# main.net
KiCad netlist of a schematic drawn in EAGLE
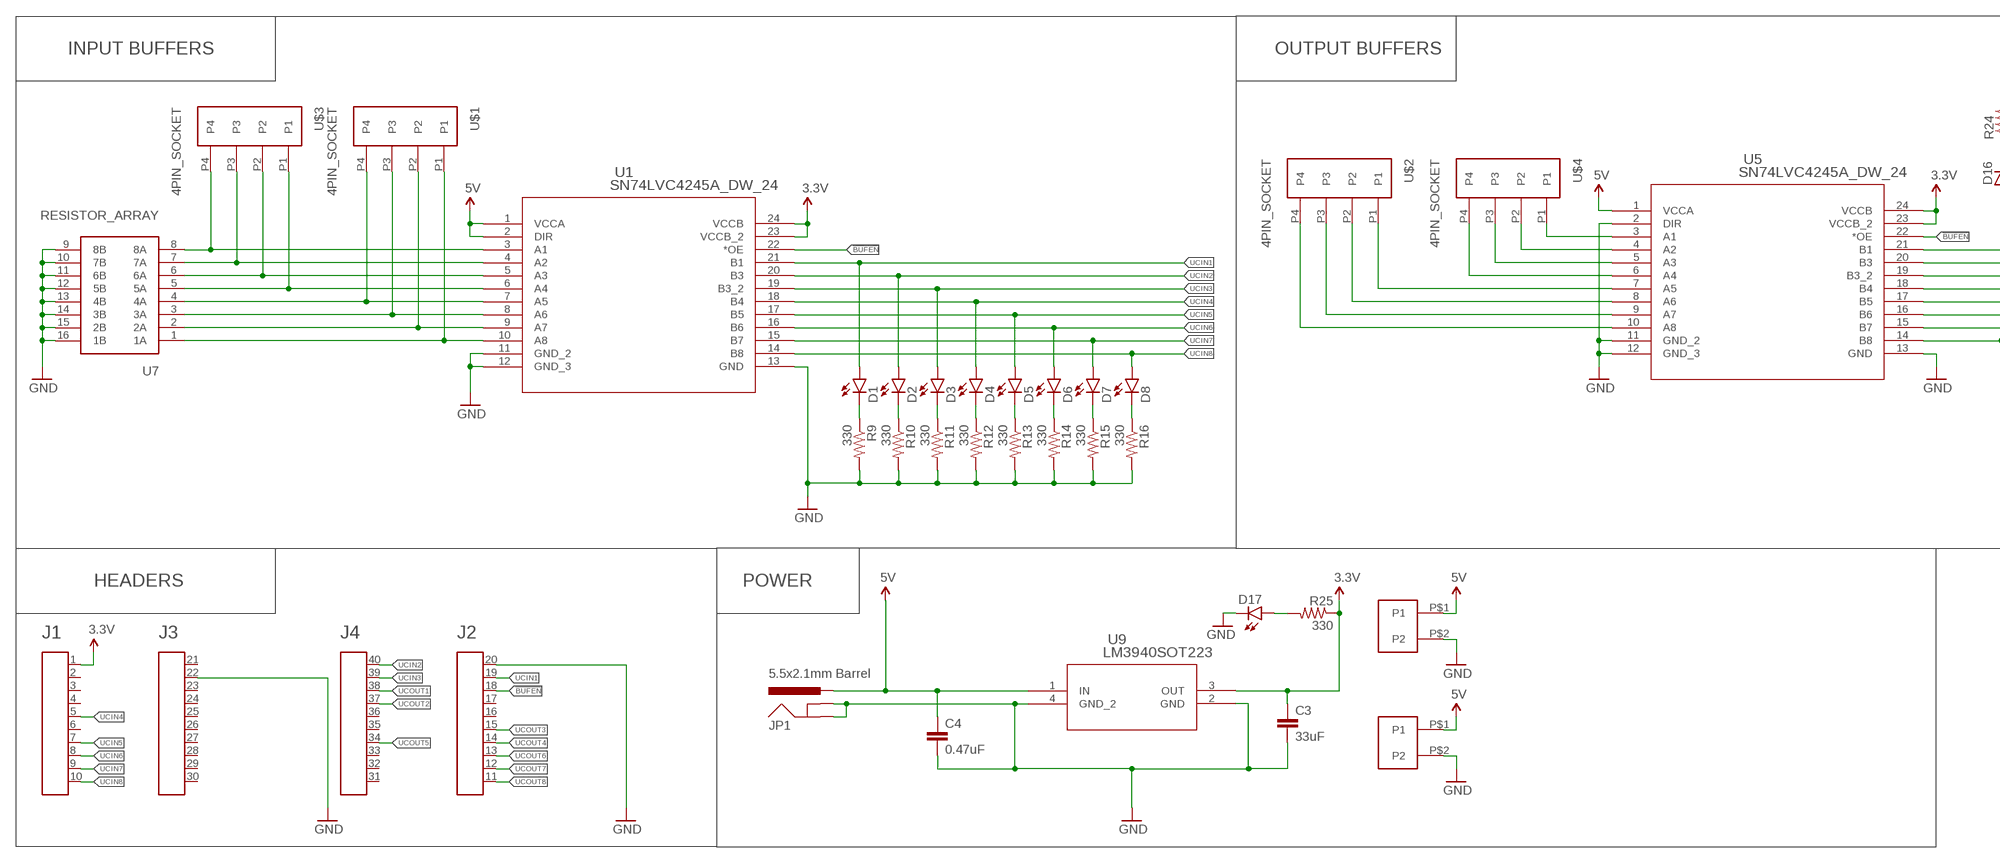
[diagram p0: schematic, sheet 1, part 1 of 2]
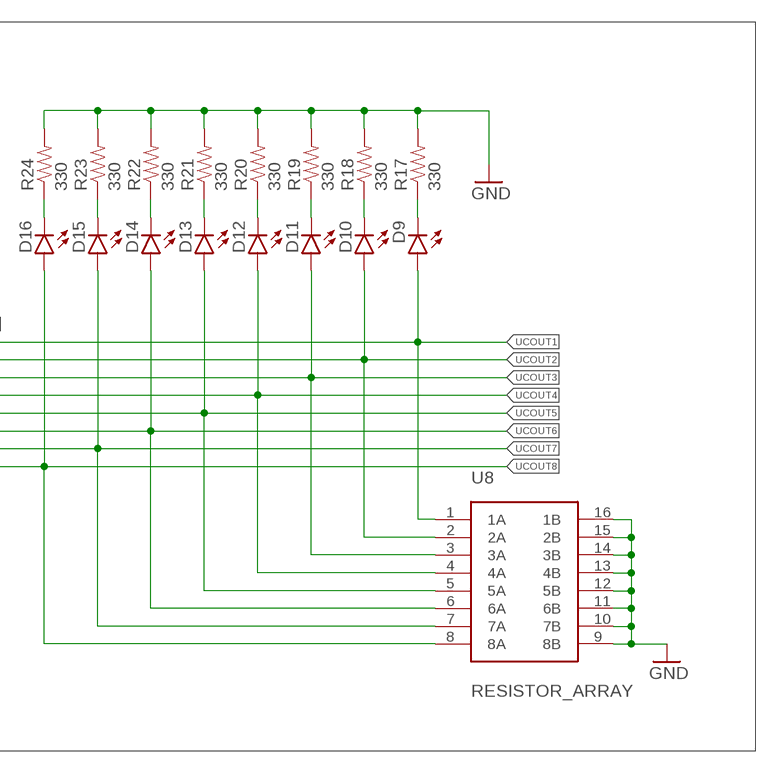
[diagram p1: schematic, sheet 1, part 2 of 2]

(export (version "E")
  (design (tool "Eeschema 10.0.6"))
  (components
    (comp (ref "A1")
      (value "HEADER4X10-BOOSTERPACK")
      (footprint "eagle-import:4X10-BOOSTERPACK")
      (libsource (lib "eagle-import") (part "HEADER4X10-BOOSTERPACK"))
    )
    (comp (ref "C3")
      (value "33uF")
      (footprint "eagle-import:1206")
      (libsource (lib "eagle-import") (part "2.2UF50V10%(1206)"))
    )
    (comp (ref "C4")
      (value "0.47uF")
      (footprint "eagle-import:0805")
      (libsource (lib "eagle-import") (part "1.0UF-25V-+80/-20(0805)"))
    )
    (comp (ref "D1")
      (value "LED3MM")
      (footprint "eagle-import:LED3MM")
      (libsource (lib "eagle-import") (part "LED3MM"))
    )
    (comp (ref "D2")
      (value "LED3MM")
      (footprint "eagle-import:LED3MM")
      (libsource (lib "eagle-import") (part "LED3MM"))
    )
    (comp (ref "D3")
      (value "LED3MM")
      (footprint "eagle-import:LED3MM")
      (libsource (lib "eagle-import") (part "LED3MM"))
    )
    (comp (ref "D4")
      (value "LED3MM")
      (footprint "eagle-import:LED3MM")
      (libsource (lib "eagle-import") (part "LED3MM"))
    )
    (comp (ref "D5")
      (value "LED3MM")
      (footprint "eagle-import:LED3MM")
      (libsource (lib "eagle-import") (part "LED3MM"))
    )
    (comp (ref "D6")
      (value "LED3MM")
      (footprint "eagle-import:LED3MM")
      (libsource (lib "eagle-import") (part "LED3MM"))
    )
    (comp (ref "D7")
      (value "LED3MM")
      (footprint "eagle-import:LED3MM")
      (libsource (lib "eagle-import") (part "LED3MM"))
    )
    (comp (ref "D8")
      (value "LED3MM")
      (footprint "eagle-import:LED3MM")
      (libsource (lib "eagle-import") (part "LED3MM"))
    )
    (comp (ref "D9")
      (value "LED3MM")
      (footprint "eagle-import:LED3MM")
      (libsource (lib "eagle-import") (part "LED3MM"))
    )
    (comp (ref "D10")
      (value "LED3MM")
      (footprint "eagle-import:LED3MM")
      (libsource (lib "eagle-import") (part "LED3MM"))
    )
    (comp (ref "D11")
      (value "LED3MM")
      (footprint "eagle-import:LED3MM")
      (libsource (lib "eagle-import") (part "LED3MM"))
    )
    (comp (ref "D12")
      (value "LED3MM")
      (footprint "eagle-import:LED3MM")
      (libsource (lib "eagle-import") (part "LED3MM"))
    )
    (comp (ref "D13")
      (value "LED3MM")
      (footprint "eagle-import:LED3MM")
      (libsource (lib "eagle-import") (part "LED3MM"))
    )
    (comp (ref "D14")
      (value "LED3MM")
      (footprint "eagle-import:LED3MM")
      (libsource (lib "eagle-import") (part "LED3MM"))
    )
    (comp (ref "D15")
      (value "LED3MM")
      (footprint "eagle-import:LED3MM")
      (libsource (lib "eagle-import") (part "LED3MM"))
    )
    (comp (ref "D16")
      (value "LED3MM")
      (footprint "eagle-import:LED3MM")
      (libsource (lib "eagle-import") (part "LED3MM"))
    )
    (comp (ref "D17")
      (value "LED3MM")
      (footprint "eagle-import:LED3MM")
      (libsource (lib "eagle-import") (part "LED3MM"))
    )
    (comp (ref "JP1")
      (value "5.5x2.1mm Barrel")
      (footprint "eagle-import:POWER_JACK_SMD")
      (libsource (lib "eagle-import") (part "POWER_JACKSMD"))
    )
    (comp (ref "R9")
      (value "330")
      (footprint "eagle-import:0805")
      (libsource (lib "eagle-import") (part "RESISTOR0805-RES"))
    )
    (comp (ref "R10")
      (value "330")
      (footprint "eagle-import:0805")
      (libsource (lib "eagle-import") (part "RESISTOR0805-RES"))
    )
    (comp (ref "R11")
      (value "330")
      (footprint "eagle-import:0805")
      (libsource (lib "eagle-import") (part "RESISTOR0805-RES"))
    )
    (comp (ref "R12")
      (value "330")
      (footprint "eagle-import:0805")
      (libsource (lib "eagle-import") (part "RESISTOR0805-RES"))
    )
    (comp (ref "R13")
      (value "330")
      (footprint "eagle-import:0805")
      (libsource (lib "eagle-import") (part "RESISTOR0805-RES"))
    )
    (comp (ref "R14")
      (value "330")
      (footprint "eagle-import:0805")
      (libsource (lib "eagle-import") (part "RESISTOR0805-RES"))
    )
    (comp (ref "R15")
      (value "330")
      (footprint "eagle-import:0805")
      (libsource (lib "eagle-import") (part "RESISTOR0805-RES"))
    )
    (comp (ref "R16")
      (value "330")
      (footprint "eagle-import:0805")
      (libsource (lib "eagle-import") (part "RESISTOR0805-RES"))
    )
    (comp (ref "R17")
      (value "330")
      (footprint "eagle-import:0805")
      (libsource (lib "eagle-import") (part "RESISTOR0805-RES"))
    )
    (comp (ref "R18")
      (value "330")
      (footprint "eagle-import:0805")
      (libsource (lib "eagle-import") (part "RESISTOR0805-RES"))
    )
    (comp (ref "R19")
      (value "330")
      (footprint "eagle-import:0805")
      (libsource (lib "eagle-import") (part "RESISTOR0805-RES"))
    )
    (comp (ref "R20")
      (value "330")
      (footprint "eagle-import:0805")
      (libsource (lib "eagle-import") (part "RESISTOR0805-RES"))
    )
    (comp (ref "R21")
      (value "330")
      (footprint "eagle-import:0805")
      (libsource (lib "eagle-import") (part "RESISTOR0805-RES"))
    )
    (comp (ref "R22")
      (value "330")
      (footprint "eagle-import:0805")
      (libsource (lib "eagle-import") (part "RESISTOR0805-RES"))
    )
    (comp (ref "R23")
      (value "330")
      (footprint "eagle-import:0805")
      (libsource (lib "eagle-import") (part "RESISTOR0805-RES"))
    )
    (comp (ref "R24")
      (value "330")
      (footprint "eagle-import:0805")
      (libsource (lib "eagle-import") (part "RESISTOR0805-RES"))
    )
    (comp (ref "R25")
      (value "330")
      (footprint "eagle-import:0805")
      (libsource (lib "eagle-import") (part "RESISTOR0805-RES"))
    )
    (comp (ref "U$1")
      (value "4PIN_SOCKET")
      (footprint "eagle-import:CONN-4PIN")
      (libsource (lib "eagle-import") (part "4PIN_SOCKET"))
    )
    (comp (ref "U$2")
      (value "4PIN_SOCKET")
      (footprint "eagle-import:CONN-4PIN")
      (libsource (lib "eagle-import") (part "4PIN_SOCKET"))
    )
    (comp (ref "U$3")
      (value "4PIN_SOCKET")
      (footprint "eagle-import:CONN-4PIN")
      (libsource (lib "eagle-import") (part "4PIN_SOCKET"))
    )
    (comp (ref "U$4")
      (value "4PIN_SOCKET")
      (footprint "eagle-import:CONN-4PIN")
      (libsource (lib "eagle-import") (part "4PIN_SOCKET"))
    )
    (comp (ref "U$5")
      (value "2PIN_SOCKET")
      (footprint "eagle-import:CONN-2PIN")
      (libsource (lib "eagle-import") (part "2PIN_SOCKET"))
    )
    (comp (ref "U$6")
      (value "2PIN_SOCKET")
      (footprint "eagle-import:CONN-2PIN")
      (libsource (lib "eagle-import") (part "2PIN_SOCKET"))
    )
    (comp (ref "U1")
      (value "SN74LVC4245A_DW_24")
      (footprint "eagle-import:DW24")
      (fields
        (field (name "GENERIC_PART_NUMBER") "SN74LVC4245A")
        (field (name "MANUFACTURER") "Texas Instruments")
        (field (name "MANUFACTURER_PART_NUMBER") "sn74lvc4245a_dw_24")
      )
      (libsource (lib "eagle-import") (part "SN74LVC4245A_DW_24"))
    )
    (comp (ref "U5")
      (value "SN74LVC4245A_DW_24")
      (footprint "eagle-import:DW24")
      (fields
        (field (name "GENERIC_PART_NUMBER") "SN74LVC4245A")
        (field (name "MANUFACTURER") "Texas Instruments")
        (field (name "MANUFACTURER_PART_NUMBER") "sn74lvc4245a_dw_24")
      )
      (libsource (lib "eagle-import") (part "SN74LVC4245A_DW_24"))
    )
    (comp (ref "U7")
      (value "RESISTOR_ARRAY")
      (footprint "eagle-import:DIL16")
      (libsource (lib "eagle-import") (part "RESISTOR_ARRAY"))
    )
    (comp (ref "U8")
      (value "RESISTOR_ARRAY")
      (footprint "eagle-import:DIL16")
      (libsource (lib "eagle-import") (part "RESISTOR_ARRAY"))
    )
    (comp (ref "U9")
      (value "LM3940SOT223")
      (footprint "eagle-import:DCY")
      (libsource (lib "eagle-import") (part "LM3940SOT223"))
    )
  )
  (nets
    (net (code "1") (name "/~{BUFEN}") (class "Default")
      (node (ref "A1") (pin "18") (pinfunction "P$18_18") (pintype "bidirectional"))
      (node (ref "U1") (pin "22") (pinfunction "*OE_22") (pintype "input"))
      (node (ref "U5") (pin "22") (pinfunction "*OE_22") (pintype "input"))
    )
    (net (code "2") (name "3.3V") (class "Default")
      (node (ref "A1") (pin "1") (pinfunction "P$1_1") (pintype "bidirectional"))
      (node (ref "C3") (pin "1") (pinfunction "1_1") (pintype "passive"))
      (node (ref "R25") (pin "1") (pinfunction "1_1") (pintype "passive"))
      (node (ref "U1") (pin "23") (pinfunction "VCCB_2_23") (pintype "power_in"))
      (node (ref "U1") (pin "24") (pinfunction "VCCB_24") (pintype "power_in"))
      (node (ref "U5") (pin "23") (pinfunction "VCCB_2_23") (pintype "power_in"))
      (node (ref "U5") (pin "24") (pinfunction "VCCB_24") (pintype "power_in"))
      (node (ref "U9") (pin "3") (pinfunction "OUT_3") (pintype "output"))
    )
    (net (code "3") (name "5V") (class "Default")
      (node (ref "C4") (pin "1") (pinfunction "1_1") (pintype "passive"))
      (node (ref "JP1") (pin "VIN0") (pinfunction "PWR_VIN0") (pintype "bidirectional"))
      (node (ref "U$5") (pin "P$1") (pinfunction "P1_P$1") (pintype "bidirectional"))
      (node (ref "U$6") (pin "P$1") (pinfunction "P1_P$1") (pintype "bidirectional"))
      (node (ref "U1") (pin "1") (pinfunction "VCCA_1") (pintype "power_in"))
      (node (ref "U1") (pin "2") (pinfunction "DIR_2") (pintype "input"))
      (node (ref "U5") (pin "1") (pinfunction "VCCA_1") (pintype "power_in"))
      (node (ref "U9") (pin "1") (pinfunction "IN_1") (pintype "input"))
    )
    (net (code "4") (name "GND") (class "Default")
      (node (ref "A1") (pin "20") (pinfunction "P$20_20") (pintype "bidirectional"))
      (node (ref "A1") (pin "22") (pinfunction "P$22_22") (pintype "bidirectional"))
      (node (ref "C3") (pin "2") (pinfunction "2_2") (pintype "passive"))
      (node (ref "C4") (pin "2") (pinfunction "2_2") (pintype "passive"))
      (node (ref "D17") (pin "K") (pinfunction "C_K") (pintype "passive"))
      (node (ref "JP1") (pin "GND") (pinfunction "GNDBREAK_GND") (pintype "bidirectional"))
      (node (ref "JP1") (pin "P$4") (pinfunction "GND_P$4") (pintype "bidirectional"))
      (node (ref "R10") (pin "2") (pinfunction "2_2") (pintype "passive"))
      (node (ref "R11") (pin "2") (pinfunction "2_2") (pintype "passive"))
      (node (ref "R12") (pin "2") (pinfunction "2_2") (pintype "passive"))
      (node (ref "R13") (pin "2") (pinfunction "2_2") (pintype "passive"))
      (node (ref "R14") (pin "2") (pinfunction "2_2") (pintype "passive"))
      (node (ref "R15") (pin "2") (pinfunction "2_2") (pintype "passive"))
      (node (ref "R16") (pin "2") (pinfunction "2_2") (pintype "passive"))
      (node (ref "R17") (pin "2") (pinfunction "2_2") (pintype "passive"))
      (node (ref "R18") (pin "2") (pinfunction "2_2") (pintype "passive"))
      (node (ref "R19") (pin "2") (pinfunction "2_2") (pintype "passive"))
      (node (ref "R20") (pin "2") (pinfunction "2_2") (pintype "passive"))
      (node (ref "R21") (pin "2") (pinfunction "2_2") (pintype "passive"))
      (node (ref "R22") (pin "2") (pinfunction "2_2") (pintype "passive"))
      (node (ref "R23") (pin "2") (pinfunction "2_2") (pintype "passive"))
      (node (ref "R24") (pin "2") (pinfunction "2_2") (pintype "passive"))
      (node (ref "R9") (pin "2") (pinfunction "2_2") (pintype "passive"))
      (node (ref "U$5") (pin "P$2") (pinfunction "P2_P$2") (pintype "bidirectional"))
      (node (ref "U$6") (pin "P$2") (pinfunction "P2_P$2") (pintype "bidirectional"))
      (node (ref "U1") (pin "11") (pinfunction "GND_2_11") (pintype "power_in"))
      (node (ref "U1") (pin "12") (pinfunction "GND_3_12") (pintype "power_in"))
      (node (ref "U1") (pin "13") (pinfunction "GND_13") (pintype "power_in"))
      (node (ref "U5") (pin "11") (pinfunction "GND_2_11") (pintype "power_in"))
      (node (ref "U5") (pin "12") (pinfunction "GND_3_12") (pintype "power_in"))
      (node (ref "U5") (pin "13") (pinfunction "GND_13") (pintype "power_in"))
      (node (ref "U5") (pin "2") (pinfunction "DIR_2") (pintype "input"))
      (node (ref "U7") (pin "10") (pinfunction "7B_10") (pintype "bidirectional"))
      (node (ref "U7") (pin "11") (pinfunction "6B_11") (pintype "bidirectional"))
      (node (ref "U7") (pin "12") (pinfunction "5B_12") (pintype "bidirectional"))
      (node (ref "U7") (pin "13") (pinfunction "4B_13") (pintype "bidirectional"))
      (node (ref "U7") (pin "14") (pinfunction "3B_14") (pintype "bidirectional"))
      (node (ref "U7") (pin "15") (pinfunction "2B_15") (pintype "bidirectional"))
      (node (ref "U7") (pin "16") (pinfunction "1B_16") (pintype "bidirectional"))
      (node (ref "U7") (pin "9") (pinfunction "8B_9") (pintype "bidirectional"))
      (node (ref "U8") (pin "10") (pinfunction "7B_10") (pintype "bidirectional"))
      (node (ref "U8") (pin "11") (pinfunction "6B_11") (pintype "bidirectional"))
      (node (ref "U8") (pin "12") (pinfunction "5B_12") (pintype "bidirectional"))
      (node (ref "U8") (pin "13") (pinfunction "4B_13") (pintype "bidirectional"))
      (node (ref "U8") (pin "14") (pinfunction "3B_14") (pintype "bidirectional"))
      (node (ref "U8") (pin "15") (pinfunction "2B_15") (pintype "bidirectional"))
      (node (ref "U8") (pin "16") (pinfunction "1B_16") (pintype "bidirectional"))
      (node (ref "U8") (pin "9") (pinfunction "8B_9") (pintype "bidirectional"))
      (node (ref "U9") (pin "2") (pinfunction "GND_2") (pintype "passive"))
      (node (ref "U9") (pin "4") (pinfunction "GND_2_4") (pintype "passive"))
    )
    (net (code "5") (name "Net-(D1-C)") (class "Default")
      (node (ref "D1") (pin "K") (pinfunction "C_K") (pintype "passive"))
      (node (ref "R9") (pin "1") (pinfunction "1_1") (pintype "passive"))
    )
    (net (code "6") (name "Net-(D2-C)") (class "Default")
      (node (ref "D2") (pin "K") (pinfunction "C_K") (pintype "passive"))
      (node (ref "R10") (pin "1") (pinfunction "1_1") (pintype "passive"))
    )
    (net (code "7") (name "Net-(D3-C)") (class "Default")
      (node (ref "D3") (pin "K") (pinfunction "C_K") (pintype "passive"))
      (node (ref "R11") (pin "1") (pinfunction "1_1") (pintype "passive"))
    )
    (net (code "8") (name "Net-(D4-C)") (class "Default")
      (node (ref "D4") (pin "K") (pinfunction "C_K") (pintype "passive"))
      (node (ref "R12") (pin "1") (pinfunction "1_1") (pintype "passive"))
    )
    (net (code "9") (name "Net-(D5-C)") (class "Default")
      (node (ref "D5") (pin "K") (pinfunction "C_K") (pintype "passive"))
      (node (ref "R13") (pin "1") (pinfunction "1_1") (pintype "passive"))
    )
    (net (code "10") (name "Net-(D6-C)") (class "Default")
      (node (ref "D6") (pin "K") (pinfunction "C_K") (pintype "passive"))
      (node (ref "R14") (pin "1") (pinfunction "1_1") (pintype "passive"))
    )
    (net (code "11") (name "Net-(D7-C)") (class "Default")
      (node (ref "D7") (pin "K") (pinfunction "C_K") (pintype "passive"))
      (node (ref "R15") (pin "1") (pinfunction "1_1") (pintype "passive"))
    )
    (net (code "12") (name "Net-(D8-C)") (class "Default")
      (node (ref "D8") (pin "K") (pinfunction "C_K") (pintype "passive"))
      (node (ref "R16") (pin "1") (pinfunction "1_1") (pintype "passive"))
    )
    (net (code "13") (name "Net-(D9-C)") (class "Default")
      (node (ref "D9") (pin "K") (pinfunction "C_K") (pintype "passive"))
      (node (ref "R17") (pin "1") (pinfunction "1_1") (pintype "passive"))
    )
    (net (code "14") (name "Net-(D10-C)") (class "Default")
      (node (ref "D10") (pin "K") (pinfunction "C_K") (pintype "passive"))
      (node (ref "R18") (pin "1") (pinfunction "1_1") (pintype "passive"))
    )
    (net (code "15") (name "Net-(D11-C)") (class "Default")
      (node (ref "D11") (pin "K") (pinfunction "C_K") (pintype "passive"))
      (node (ref "R19") (pin "1") (pinfunction "1_1") (pintype "passive"))
    )
    (net (code "16") (name "Net-(D12-C)") (class "Default")
      (node (ref "D12") (pin "K") (pinfunction "C_K") (pintype "passive"))
      (node (ref "R20") (pin "1") (pinfunction "1_1") (pintype "passive"))
    )
    (net (code "17") (name "Net-(D13-C)") (class "Default")
      (node (ref "D13") (pin "K") (pinfunction "C_K") (pintype "passive"))
      (node (ref "R21") (pin "1") (pinfunction "1_1") (pintype "passive"))
    )
    (net (code "18") (name "Net-(D14-C)") (class "Default")
      (node (ref "D14") (pin "K") (pinfunction "C_K") (pintype "passive"))
      (node (ref "R22") (pin "1") (pinfunction "1_1") (pintype "passive"))
    )
    (net (code "19") (name "Net-(D15-C)") (class "Default")
      (node (ref "D15") (pin "K") (pinfunction "C_K") (pintype "passive"))
      (node (ref "R23") (pin "1") (pinfunction "1_1") (pintype "passive"))
    )
    (net (code "20") (name "Net-(D16-C)") (class "Default")
      (node (ref "D16") (pin "K") (pinfunction "C_K") (pintype "passive"))
      (node (ref "R24") (pin "1") (pinfunction "1_1") (pintype "passive"))
    )
    (net (code "21") (name "Net-(D17-PadA)") (class "Default")
      (node (ref "D17") (pin "A") (pinfunction "A_A") (pintype "passive"))
      (node (ref "R25") (pin "2") (pinfunction "2_2") (pintype "passive"))
    )
    (net (code "22") (name "Net-(U1-A1)") (class "Default")
      (node (ref "U$3") (pin "P4") (pinfunction "P4_P4") (pintype "bidirectional"))
      (node (ref "U1") (pin "3") (pinfunction "A1_3") (pintype "bidirectional"))
      (node (ref "U7") (pin "8") (pinfunction "8A_8") (pintype "bidirectional"))
    )
    (net (code "23") (name "Net-(U1-A2)") (class "Default")
      (node (ref "U$3") (pin "P3") (pinfunction "P3_P3") (pintype "bidirectional"))
      (node (ref "U1") (pin "4") (pinfunction "A2_4") (pintype "bidirectional"))
      (node (ref "U7") (pin "7") (pinfunction "7A_7") (pintype "bidirectional"))
    )
    (net (code "24") (name "Net-(U1-A3)") (class "Default")
      (node (ref "U$3") (pin "P2") (pinfunction "P2_P2") (pintype "bidirectional"))
      (node (ref "U1") (pin "5") (pinfunction "A3_5") (pintype "bidirectional"))
      (node (ref "U7") (pin "6") (pinfunction "6A_6") (pintype "bidirectional"))
    )
    (net (code "25") (name "Net-(U1-A4)") (class "Default")
      (node (ref "U$3") (pin "P1") (pinfunction "P1_P1") (pintype "bidirectional"))
      (node (ref "U1") (pin "6") (pinfunction "A4_6") (pintype "bidirectional"))
      (node (ref "U7") (pin "5") (pinfunction "5A_5") (pintype "bidirectional"))
    )
    (net (code "26") (name "Net-(U1-A5)") (class "Default")
      (node (ref "U$1") (pin "P4") (pinfunction "P4_P4") (pintype "bidirectional"))
      (node (ref "U1") (pin "7") (pinfunction "A5_7") (pintype "bidirectional"))
      (node (ref "U7") (pin "4") (pinfunction "4A_4") (pintype "bidirectional"))
    )
    (net (code "27") (name "Net-(U1-A6)") (class "Default")
      (node (ref "U$1") (pin "P3") (pinfunction "P3_P3") (pintype "bidirectional"))
      (node (ref "U1") (pin "8") (pinfunction "A6_8") (pintype "bidirectional"))
      (node (ref "U7") (pin "3") (pinfunction "3A_3") (pintype "bidirectional"))
    )
    (net (code "28") (name "Net-(U1-A7)") (class "Default")
      (node (ref "U$1") (pin "P2") (pinfunction "P2_P2") (pintype "bidirectional"))
      (node (ref "U1") (pin "9") (pinfunction "A7_9") (pintype "bidirectional"))
      (node (ref "U7") (pin "2") (pinfunction "2A_2") (pintype "bidirectional"))
    )
    (net (code "29") (name "Net-(U1-A8)") (class "Default")
      (node (ref "U$1") (pin "P1") (pinfunction "P1_P1") (pintype "bidirectional"))
      (node (ref "U1") (pin "10") (pinfunction "A8_10") (pintype "bidirectional"))
      (node (ref "U7") (pin "1") (pinfunction "1A_1") (pintype "bidirectional"))
    )
    (net (code "30") (name "Net-(U5-A1)") (class "Default")
      (node (ref "U$4") (pin "P1") (pinfunction "P1_P1") (pintype "bidirectional"))
      (node (ref "U5") (pin "3") (pinfunction "A1_3") (pintype "bidirectional"))
    )
    (net (code "31") (name "Net-(U5-A2)") (class "Default")
      (node (ref "U$4") (pin "P2") (pinfunction "P2_P2") (pintype "bidirectional"))
      (node (ref "U5") (pin "4") (pinfunction "A2_4") (pintype "bidirectional"))
    )
    (net (code "32") (name "Net-(U5-A3)") (class "Default")
      (node (ref "U$4") (pin "P3") (pinfunction "P3_P3") (pintype "bidirectional"))
      (node (ref "U5") (pin "5") (pinfunction "A3_5") (pintype "bidirectional"))
    )
    (net (code "33") (name "Net-(U5-A4)") (class "Default")
      (node (ref "U$4") (pin "P4") (pinfunction "P4_P4") (pintype "bidirectional"))
      (node (ref "U5") (pin "6") (pinfunction "A4_6") (pintype "bidirectional"))
    )
    (net (code "34") (name "Net-(U5-A5)") (class "Default")
      (node (ref "U$2") (pin "P1") (pinfunction "P1_P1") (pintype "bidirectional"))
      (node (ref "U5") (pin "7") (pinfunction "A5_7") (pintype "bidirectional"))
    )
    (net (code "35") (name "Net-(U5-A6)") (class "Default")
      (node (ref "U$2") (pin "P2") (pinfunction "P2_P2") (pintype "bidirectional"))
      (node (ref "U5") (pin "8") (pinfunction "A6_8") (pintype "bidirectional"))
    )
    (net (code "36") (name "Net-(U5-A7)") (class "Default")
      (node (ref "U$2") (pin "P3") (pinfunction "P3_P3") (pintype "bidirectional"))
      (node (ref "U5") (pin "9") (pinfunction "A7_9") (pintype "bidirectional"))
    )
    (net (code "37") (name "Net-(U5-A8)") (class "Default")
      (node (ref "U$2") (pin "P4") (pinfunction "P4_P4") (pintype "bidirectional"))
      (node (ref "U5") (pin "10") (pinfunction "A8_10") (pintype "bidirectional"))
    )
    (net (code "38") (name "UCIN1") (class "Default")
      (node (ref "A1") (pin "19") (pinfunction "P$19_19") (pintype "bidirectional"))
      (node (ref "D1") (pin "A") (pinfunction "A_A") (pintype "passive"))
      (node (ref "U1") (pin "21") (pinfunction "B1_21") (pintype "bidirectional"))
    )
    (net (code "39") (name "UCIN2") (class "Default")
      (node (ref "A1") (pin "40") (pinfunction "P$40_40") (pintype "bidirectional"))
      (node (ref "D2") (pin "A") (pinfunction "A_A") (pintype "passive"))
      (node (ref "U1") (pin "20") (pinfunction "B3_20") (pintype "bidirectional"))
    )
    (net (code "40") (name "UCIN3") (class "Default")
      (node (ref "A1") (pin "39") (pinfunction "P$39_39") (pintype "bidirectional"))
      (node (ref "D3") (pin "A") (pinfunction "A_A") (pintype "passive"))
      (node (ref "U1") (pin "19") (pinfunction "B3_2_19") (pintype "bidirectional"))
    )
    (net (code "41") (name "UCIN4") (class "Default")
      (node (ref "A1") (pin "5") (pinfunction "P$5_5") (pintype "bidirectional"))
      (node (ref "D4") (pin "A") (pinfunction "A_A") (pintype "passive"))
      (node (ref "U1") (pin "18") (pinfunction "B4_18") (pintype "bidirectional"))
    )
    (net (code "42") (name "UCIN5") (class "Default")
      (node (ref "A1") (pin "7") (pinfunction "P$7_7") (pintype "bidirectional"))
      (node (ref "D5") (pin "A") (pinfunction "A_A") (pintype "passive"))
      (node (ref "U1") (pin "17") (pinfunction "B5_17") (pintype "bidirectional"))
    )
    (net (code "43") (name "UCIN6") (class "Default")
      (node (ref "A1") (pin "8") (pinfunction "P$8_8") (pintype "bidirectional"))
      (node (ref "D6") (pin "A") (pinfunction "A_A") (pintype "passive"))
      (node (ref "U1") (pin "16") (pinfunction "B6_16") (pintype "bidirectional"))
    )
    (net (code "44") (name "UCIN7") (class "Default")
      (node (ref "A1") (pin "9") (pinfunction "P$9_9") (pintype "bidirectional"))
      (node (ref "D7") (pin "A") (pinfunction "A_A") (pintype "passive"))
      (node (ref "U1") (pin "15") (pinfunction "B7_15") (pintype "bidirectional"))
    )
    (net (code "45") (name "UCIN8") (class "Default")
      (node (ref "A1") (pin "10") (pinfunction "P$10_10") (pintype "bidirectional"))
      (node (ref "D8") (pin "A") (pinfunction "A_A") (pintype "passive"))
      (node (ref "U1") (pin "14") (pinfunction "B8_14") (pintype "bidirectional"))
    )
    (net (code "46") (name "UCOUT1") (class "Default")
      (node (ref "A1") (pin "38") (pinfunction "P$38_38") (pintype "bidirectional"))
      (node (ref "D9") (pin "A") (pinfunction "A_A") (pintype "passive"))
      (node (ref "U5") (pin "21") (pinfunction "B1_21") (pintype "bidirectional"))
      (node (ref "U8") (pin "1") (pinfunction "1A_1") (pintype "bidirectional"))
    )
    (net (code "47") (name "UCOUT2") (class "Default")
      (node (ref "A1") (pin "37") (pinfunction "P$37_37") (pintype "bidirectional"))
      (node (ref "D10") (pin "A") (pinfunction "A_A") (pintype "passive"))
      (node (ref "U5") (pin "20") (pinfunction "B3_20") (pintype "bidirectional"))
      (node (ref "U8") (pin "2") (pinfunction "2A_2") (pintype "bidirectional"))
    )
    (net (code "48") (name "UCOUT3") (class "Default")
      (node (ref "A1") (pin "15") (pinfunction "P$15_15") (pintype "bidirectional"))
      (node (ref "D11") (pin "A") (pinfunction "A_A") (pintype "passive"))
      (node (ref "U5") (pin "19") (pinfunction "B3_2_19") (pintype "bidirectional"))
      (node (ref "U8") (pin "3") (pinfunction "3A_3") (pintype "bidirectional"))
    )
    (net (code "49") (name "UCOUT4") (class "Default")
      (node (ref "A1") (pin "14") (pinfunction "P$14_14") (pintype "bidirectional"))
      (node (ref "D12") (pin "A") (pinfunction "A_A") (pintype "passive"))
      (node (ref "U5") (pin "18") (pinfunction "B4_18") (pintype "bidirectional"))
      (node (ref "U8") (pin "4") (pinfunction "4A_4") (pintype "bidirectional"))
    )
    (net (code "50") (name "UCOUT5") (class "Default")
      (node (ref "A1") (pin "34") (pinfunction "P$34_34") (pintype "bidirectional"))
      (node (ref "D13") (pin "A") (pinfunction "A_A") (pintype "passive"))
      (node (ref "U5") (pin "17") (pinfunction "B5_17") (pintype "bidirectional"))
      (node (ref "U8") (pin "5") (pinfunction "5A_5") (pintype "bidirectional"))
    )
    (net (code "51") (name "UCOUT6") (class "Default")
      (node (ref "A1") (pin "13") (pinfunction "P$13_13") (pintype "bidirectional"))
      (node (ref "D14") (pin "A") (pinfunction "A_A") (pintype "passive"))
      (node (ref "U5") (pin "16") (pinfunction "B6_16") (pintype "bidirectional"))
      (node (ref "U8") (pin "6") (pinfunction "6A_6") (pintype "bidirectional"))
    )
    (net (code "52") (name "UCOUT7") (class "Default")
      (node (ref "A1") (pin "12") (pinfunction "P$12_12") (pintype "bidirectional"))
      (node (ref "D15") (pin "A") (pinfunction "A_A") (pintype "passive"))
      (node (ref "U5") (pin "15") (pinfunction "B7_15") (pintype "bidirectional"))
      (node (ref "U8") (pin "7") (pinfunction "7A_7") (pintype "bidirectional"))
    )
    (net (code "53") (name "UCOUT8") (class "Default")
      (node (ref "A1") (pin "11") (pinfunction "P$11_11") (pintype "bidirectional"))
      (node (ref "D16") (pin "A") (pinfunction "A_A") (pintype "passive"))
      (node (ref "U5") (pin "14") (pinfunction "B8_14") (pintype "bidirectional"))
      (node (ref "U8") (pin "8") (pinfunction "8A_8") (pintype "bidirectional"))
    )
    (net (code "54") (name "unconnected-(A1-P$2-Pad2)") (class "Default")
      (node (ref "A1") (pin "2") (pinfunction "P$2_2") (pintype "bidirectional"))
    )
    (net (code "55") (name "unconnected-(A1-P$3-Pad3)") (class "Default")
      (node (ref "A1") (pin "3") (pinfunction "P$3_3") (pintype "bidirectional"))
    )
    (net (code "56") (name "unconnected-(A1-P$4-Pad4)") (class "Default")
      (node (ref "A1") (pin "4") (pinfunction "P$4_4") (pintype "bidirectional"))
    )
    (net (code "57") (name "unconnected-(A1-P$6-Pad6)") (class "Default")
      (node (ref "A1") (pin "6") (pinfunction "P$6_6") (pintype "bidirectional"))
    )
    (net (code "58") (name "unconnected-(A1-P$16-Pad16)") (class "Default")
      (node (ref "A1") (pin "16") (pinfunction "P$16_16") (pintype "bidirectional"))
    )
    (net (code "59") (name "unconnected-(A1-P$17-Pad17)") (class "Default")
      (node (ref "A1") (pin "17") (pinfunction "P$17_17") (pintype "bidirectional"))
    )
    (net (code "60") (name "unconnected-(A1-P$21-Pad21)") (class "Default")
      (node (ref "A1") (pin "21") (pinfunction "P$21_21") (pintype "bidirectional"))
    )
    (net (code "61") (name "unconnected-(A1-P$23-Pad23)") (class "Default")
      (node (ref "A1") (pin "23") (pinfunction "P$23_23") (pintype "bidirectional"))
    )
    (net (code "62") (name "unconnected-(A1-P$24-Pad24)") (class "Default")
      (node (ref "A1") (pin "24") (pinfunction "P$24_24") (pintype "bidirectional"))
    )
    (net (code "63") (name "unconnected-(A1-P$25-Pad25)") (class "Default")
      (node (ref "A1") (pin "25") (pinfunction "P$25_25") (pintype "bidirectional"))
    )
    (net (code "64") (name "unconnected-(A1-P$26-Pad26)") (class "Default")
      (node (ref "A1") (pin "26") (pinfunction "P$26_26") (pintype "bidirectional"))
    )
    (net (code "65") (name "unconnected-(A1-P$27-Pad27)") (class "Default")
      (node (ref "A1") (pin "27") (pinfunction "P$27_27") (pintype "bidirectional"))
    )
    (net (code "66") (name "unconnected-(A1-P$28-Pad28)") (class "Default")
      (node (ref "A1") (pin "28") (pinfunction "P$28_28") (pintype "bidirectional"))
    )
    (net (code "67") (name "unconnected-(A1-P$29-Pad29)") (class "Default")
      (node (ref "A1") (pin "29") (pinfunction "P$29_29") (pintype "bidirectional"))
    )
    (net (code "68") (name "unconnected-(A1-P$30-Pad30)") (class "Default")
      (node (ref "A1") (pin "30") (pinfunction "P$30_30") (pintype "bidirectional"))
    )
    (net (code "69") (name "unconnected-(A1-P$31-Pad31)") (class "Default")
      (node (ref "A1") (pin "31") (pinfunction "P$31_31") (pintype "bidirectional"))
    )
    (net (code "70") (name "unconnected-(A1-P$32-Pad32)") (class "Default")
      (node (ref "A1") (pin "32") (pinfunction "P$32_32") (pintype "bidirectional"))
    )
    (net (code "71") (name "unconnected-(A1-P$33-Pad33)") (class "Default")
      (node (ref "A1") (pin "33") (pinfunction "P$33_33") (pintype "bidirectional"))
    )
    (net (code "72") (name "unconnected-(A1-P$35-Pad35)") (class "Default")
      (node (ref "A1") (pin "35") (pinfunction "P$35_35") (pintype "bidirectional"))
    )
    (net (code "73") (name "unconnected-(A1-P$36-Pad36)") (class "Default")
      (node (ref "A1") (pin "36") (pinfunction "P$36_36") (pintype "bidirectional"))
    )
  )
)
